# Chasis_2018.net
KiCad netlist of a schematic drawn in EAGLE
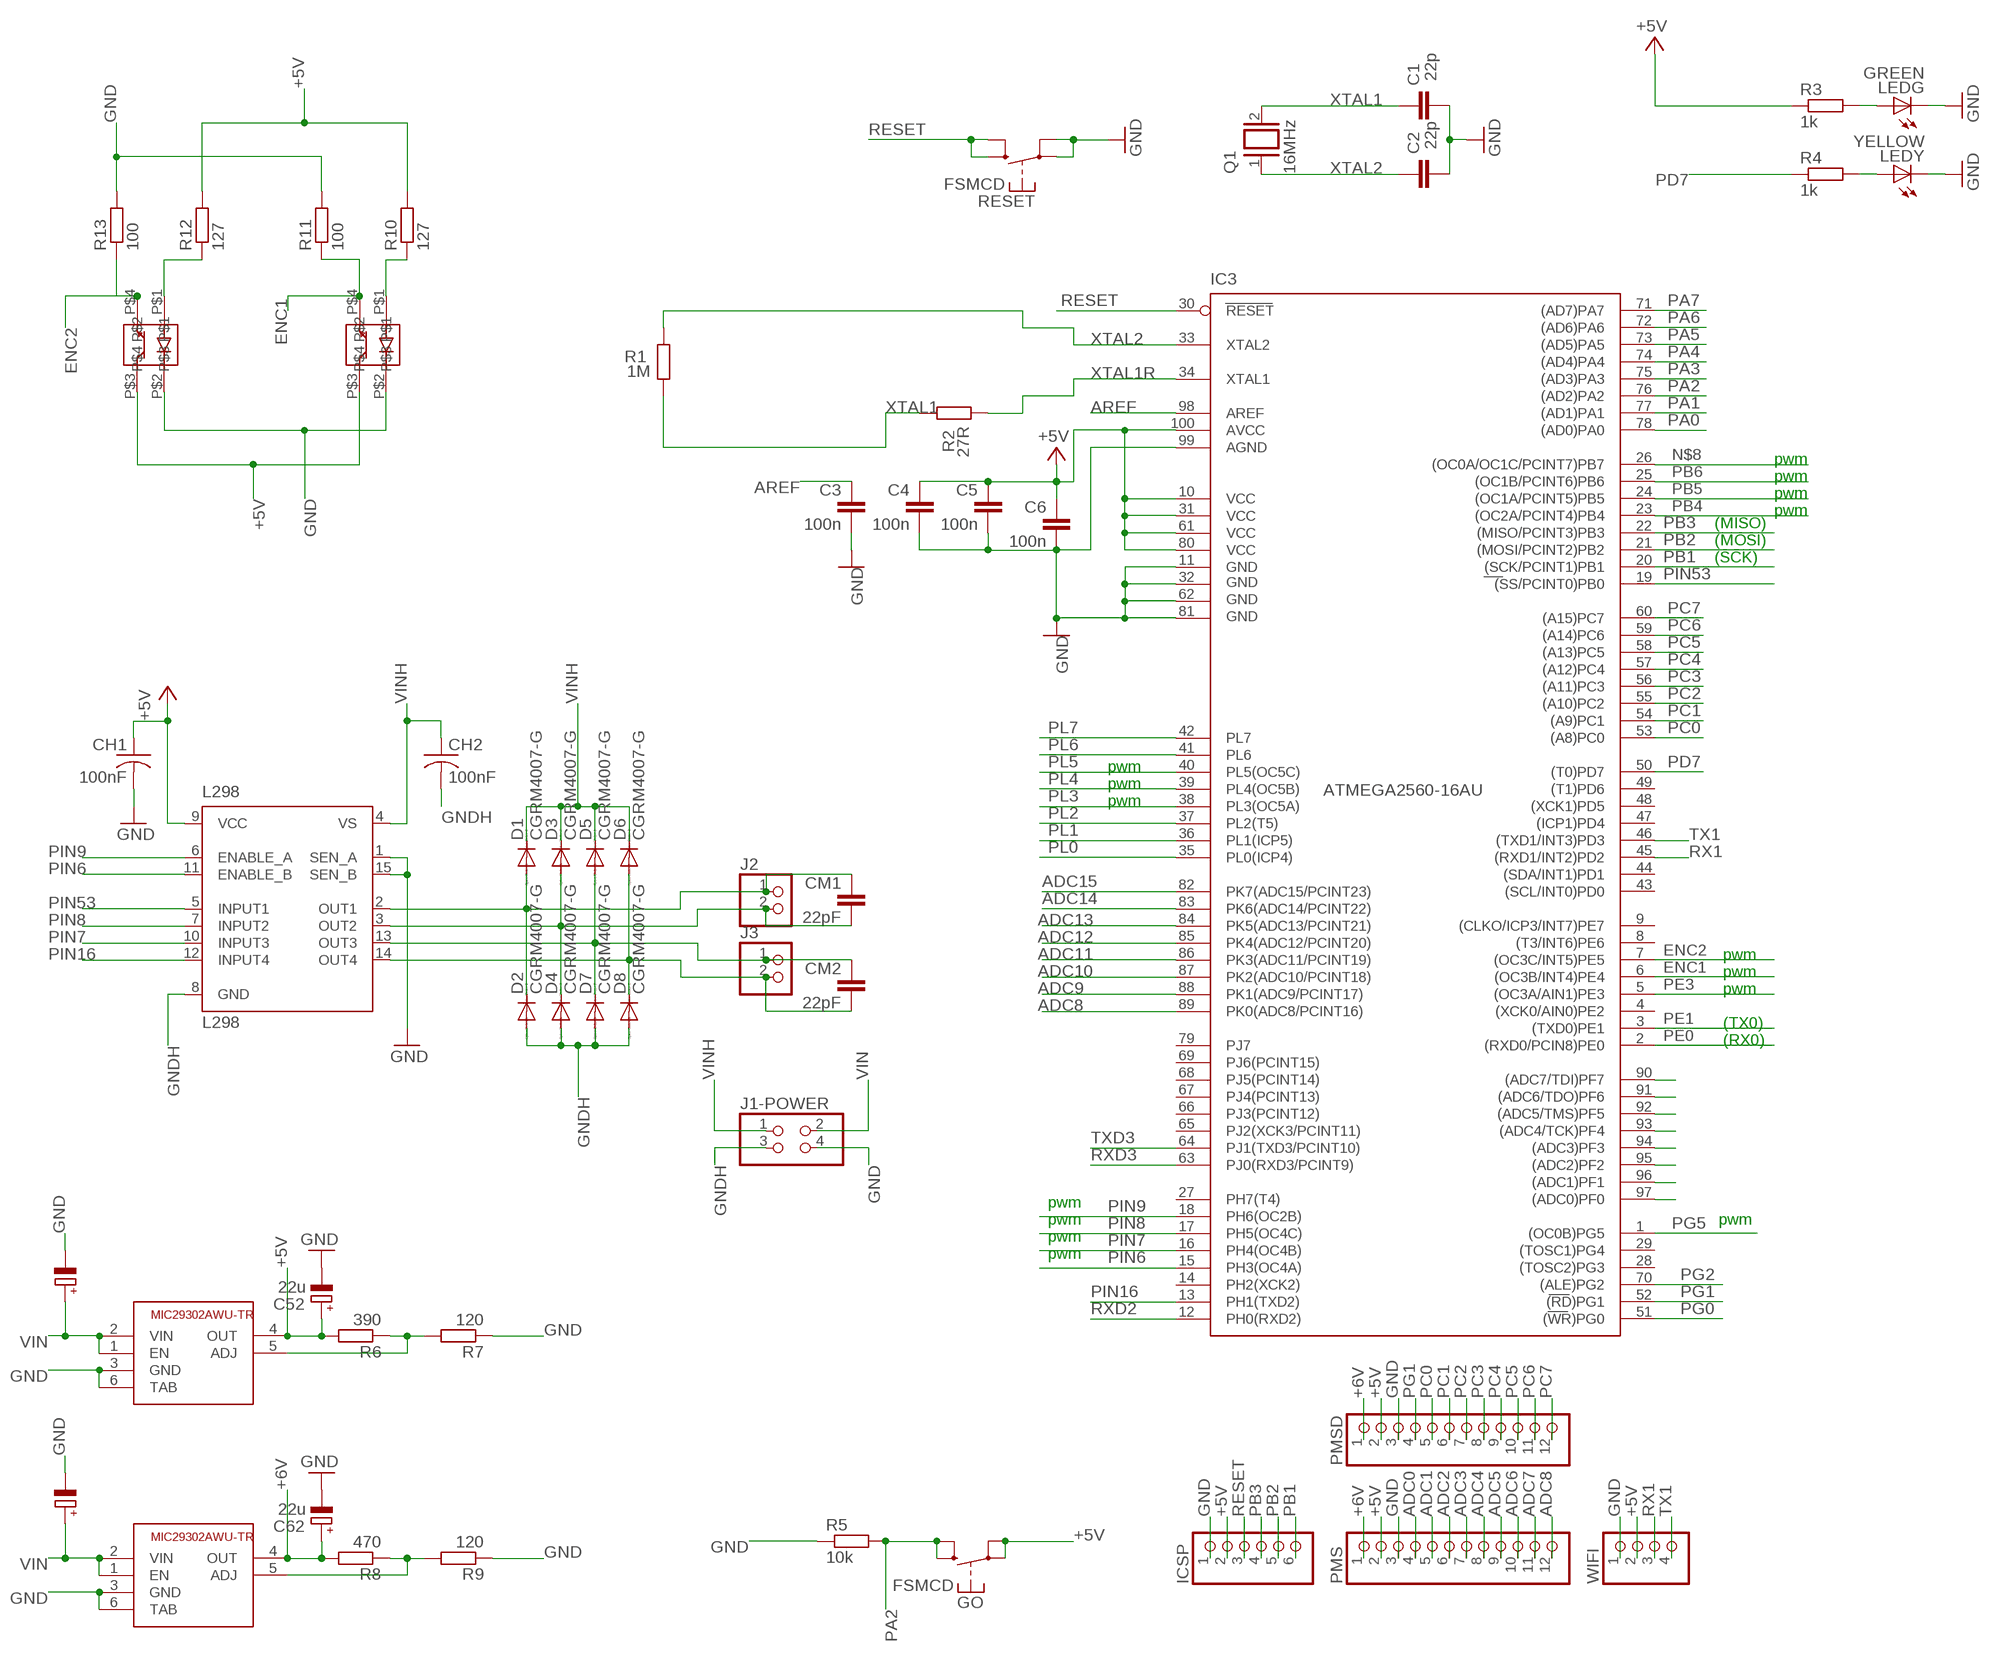
[diagram p0: schematic, sheet 1]

(export (version "E")
  (design (tool "Eeschema 10.0.6"))
  (components
    (comp (ref "C1")
      (value "22p")
      (footprint "eagle-import:C0805K")
      (libsource (lib "eagle-import") (part "C-EUC0805K"))
    )
    (comp (ref "C2")
      (value "22p")
      (footprint "eagle-import:C0805K")
      (libsource (lib "eagle-import") (part "C-EUC0805K"))
    )
    (comp (ref "C3")
      (value "100n")
      (footprint "eagle-import:C0805K")
      (libsource (lib "eagle-import") (part "C-EUC0805K"))
    )
    (comp (ref "C4")
      (value "100n")
      (footprint "eagle-import:C0805K")
      (libsource (lib "eagle-import") (part "C-EUC0805K"))
    )
    (comp (ref "C5")
      (value "100n")
      (footprint "eagle-import:C0805K")
      (libsource (lib "eagle-import") (part "C-EUC0805K"))
    )
    (comp (ref "C6")
      (value "100n")
      (footprint "eagle-import:C0805K")
      (libsource (lib "eagle-import") (part "C-EUC0805K"))
    )
    (comp (ref "C51")
      (value "10u")
      (footprint "eagle-import:PANASONIC_D")
      (libsource (lib "eagle-import") (part "CPOL-EUD"))
    )
    (comp (ref "C52")
      (value "22u")
      (footprint "eagle-import:PANASONIC_D")
      (libsource (lib "eagle-import") (part "CPOL-EUD"))
    )
    (comp (ref "C61")
      (value "10u")
      (footprint "eagle-import:PANASONIC_D")
      (libsource (lib "eagle-import") (part "CPOL-EUD"))
    )
    (comp (ref "C62")
      (value "22u")
      (footprint "eagle-import:PANASONIC_D")
      (libsource (lib "eagle-import") (part "CPOL-EUD"))
    )
    (comp (ref "CH1")
      (value "100nF")
      (footprint "eagle-import:C0805K")
      (libsource (lib "eagle-import") (part "C-USC0805K"))
    )
    (comp (ref "CH2")
      (value "100nF")
      (footprint "eagle-import:C0805K")
      (libsource (lib "eagle-import") (part "C-USC0805K"))
    )
    (comp (ref "CM1")
      (value "22pF")
      (footprint "eagle-import:C1206K")
      (libsource (lib "eagle-import") (part "C-EUC1206K"))
    )
    (comp (ref "CM2")
      (value "22pF")
      (footprint "eagle-import:C1206K")
      (libsource (lib "eagle-import") (part "C-EUC1206K"))
    )
    (comp (ref "D1")
      (value "CGRM4007-G")
      (footprint "eagle-import:SOD-123_MINI-SMA")
      (libsource (lib "eagle-import") (part "CGRM400-G7"))
    )
    (comp (ref "D2")
      (value "CGRM4007-G")
      (footprint "eagle-import:SOD-123_MINI-SMA")
      (libsource (lib "eagle-import") (part "CGRM400-G7"))
    )
    (comp (ref "D3")
      (value "CGRM4007-G")
      (footprint "eagle-import:SOD-123_MINI-SMA")
      (libsource (lib "eagle-import") (part "CGRM400-G7"))
    )
    (comp (ref "D4")
      (value "CGRM4007-G")
      (footprint "eagle-import:SOD-123_MINI-SMA")
      (libsource (lib "eagle-import") (part "CGRM400-G7"))
    )
    (comp (ref "D5")
      (value "CGRM4007-G")
      (footprint "eagle-import:SOD-123_MINI-SMA")
      (libsource (lib "eagle-import") (part "CGRM400-G7"))
    )
    (comp (ref "D6")
      (value "CGRM4007-G")
      (footprint "eagle-import:SOD-123_MINI-SMA")
      (libsource (lib "eagle-import") (part "CGRM400-G7"))
    )
    (comp (ref "D7")
      (value "CGRM4007-G")
      (footprint "eagle-import:SOD-123_MINI-SMA")
      (libsource (lib "eagle-import") (part "CGRM400-G7"))
    )
    (comp (ref "D8")
      (value "CGRM4007-G")
      (footprint "eagle-import:SOD-123_MINI-SMA")
      (libsource (lib "eagle-import") (part "CGRM400-G7"))
    )
    (comp (ref "ENC1")
      (value "EE-SX1046")
      (footprint "eagle-import:EE-SX1046")
      (libsource (lib "eagle-import") (part "EE-SX1046"))
    )
    (comp (ref "ENC2")
      (value "EE-SX1046")
      (footprint "eagle-import:EE-SX1046")
      (libsource (lib "eagle-import") (part "EE-SX1046"))
    )
    (comp (ref "GO")
      (value "FSMCD")
      (footprint "eagle-import:FSMCD")
      (libsource (lib "eagle-import") (part "FSMCD"))
    )
    (comp (ref "IC3")
      (value "ATMEGA2560-16AU")
      (footprint "eagle-import:TQFP100")
      (libsource (lib "eagle-import") (part "ATMEGAAU1280-16"))
    )
    (comp (ref "ICSP")
      (value "PINHD-1X6")
      (footprint "eagle-import:1X06")
      (libsource (lib "eagle-import") (part "PINHD-1X6"))
    )
    (comp (ref "J1-POWER")
      (value "PINHD-2X2")
      (footprint "eagle-import:2X02")
      (libsource (lib "eagle-import") (part "PINHD-2X2"))
    )
    (comp (ref "J2")
      (value "PINHD-1X2")
      (footprint "eagle-import:1X02")
      (libsource (lib "eagle-import") (part "PINHD-1X2"))
    )
    (comp (ref "J3")
      (value "PINHD-1X2")
      (footprint "eagle-import:1X02")
      (libsource (lib "eagle-import") (part "PINHD-1X2"))
    )
    (comp (ref "L298")
      (value "L298")
      (footprint "eagle-import:MULTIWATT-15")
      (fields (field (name "MPN") "L298N"))
      (libsource (lib "eagle-import") (part "L298"))
    )
    (comp (ref "LEDG")
      (value "GREEN")
      (footprint "eagle-import:CHIP-LED0805")
      (libsource (lib "eagle-import") (part "LEDCHIP-LED0805"))
    )
    (comp (ref "LEDY")
      (value "YELLOW")
      (footprint "eagle-import:CHIP-LED0805")
      (libsource (lib "eagle-import") (part "LEDCHIP-LED0805"))
    )
    (comp (ref "PMS")
      (value "PINHD-1X12")
      (footprint "eagle-import:1X12")
      (libsource (lib "eagle-import") (part "PINHD-1X12"))
    )
    (comp (ref "PMSD")
      (value "PINHD-1X12")
      (footprint "eagle-import:1X12")
      (libsource (lib "eagle-import") (part "PINHD-1X12"))
    )
    (comp (ref "Q1")
      (value "16MHz")
      (footprint "eagle-import:QS")
      (libsource (lib "eagle-import") (part "XTAL/S"))
    )
    (comp (ref "R1")
      (value "1M")
      (footprint "eagle-import:R0805W")
      (libsource (lib "eagle-import") (part "R-EU_R0805W"))
    )
    (comp (ref "R2")
      (value "27R")
      (footprint "eagle-import:R0805W")
      (libsource (lib "eagle-import") (part "R-EU_R0805W"))
    )
    (comp (ref "R3")
      (value "1k")
      (footprint "eagle-import:R0805W")
      (libsource (lib "eagle-import") (part "resistor_348_R-EU_R0805W"))
    )
    (comp (ref "R4")
      (value "1k")
      (footprint "eagle-import:R0805W")
      (libsource (lib "eagle-import") (part "resistor_348_R-EU_R0805W"))
    )
    (comp (ref "R5")
      (value "10k")
      (footprint "eagle-import:R0805W")
      (libsource (lib "eagle-import") (part "resistor_348_R-EU_R0805W"))
    )
    (comp (ref "R6")
      (value "390")
      (footprint "eagle-import:R0805W")
      (libsource (lib "eagle-import") (part "resistor_348_R-EU_R0805W"))
    )
    (comp (ref "R7")
      (value "120")
      (footprint "eagle-import:R0805W")
      (libsource (lib "eagle-import") (part "resistor_348_R-EU_R0805W"))
    )
    (comp (ref "R8")
      (value "470")
      (footprint "eagle-import:R0805W")
      (libsource (lib "eagle-import") (part "resistor_348_R-EU_R0805W"))
    )
    (comp (ref "R9")
      (value "120")
      (footprint "eagle-import:R0805W")
      (libsource (lib "eagle-import") (part "resistor_348_R-EU_R0805W"))
    )
    (comp (ref "R10")
      (value "127")
      (footprint "eagle-import:R0805W")
      (libsource (lib "eagle-import") (part "resistor_348_R-EU_R0805W"))
    )
    (comp (ref "R11")
      (value "100")
      (footprint "eagle-import:R0805W")
      (libsource (lib "eagle-import") (part "resistor_348_R-EU_R0805W"))
    )
    (comp (ref "R12")
      (value "127")
      (footprint "eagle-import:R0805W")
      (libsource (lib "eagle-import") (part "resistor_348_R-EU_R0805W"))
    )
    (comp (ref "R13")
      (value "100")
      (footprint "eagle-import:R0805W")
      (libsource (lib "eagle-import") (part "resistor_348_R-EU_R0805W"))
    )
    (comp (ref "REG5V")
      (value "MIC29302AWU-TR")
      (footprint "eagle-import:TO263-5")
      (fields (field (name "MF") "Microchip"))
      (libsource (lib "eagle-import") (part "MIC29302AWU-TR"))
    )
    (comp (ref "REG6V")
      (value "MIC29302AWU-TR")
      (footprint "eagle-import:TO263-5")
      (fields (field (name "MF") "Microchip") (field (name "SPICEPREFIX") "X"))
      (libsource (lib "eagle-import") (part "MIC29302AWU-TR"))
    )
    (comp (ref "RESET")
      (value "FSMCD")
      (footprint "eagle-import:FSMCD")
      (libsource (lib "eagle-import") (part "FSMCD"))
    )
    (comp (ref "WIFI")
      (value "PINHD-1X4")
      (footprint "eagle-import:1X04")
      (libsource (lib "eagle-import") (part "PINHD-1X4"))
    )
  )
  (nets
    (net (code "1") (name "+5V") (class "Default")
      (node (ref "C4") (pin "1") (pinfunction "1_1") (pintype "passive"))
      (node (ref "C5") (pin "1") (pinfunction "1_1") (pintype "passive"))
      (node (ref "C52") (pin "+") (pinfunction "+_+") (pintype "passive"))
      (node (ref "C6") (pin "1") (pinfunction "1_1") (pintype "passive"))
      (node (ref "CH1") (pin "1") (pinfunction "1_1") (pintype "passive"))
      (node (ref "ENC1") (pin "P$3") (pinfunction "P$2_P$3") (pintype "bidirectional"))
      (node (ref "ENC2") (pin "P$3") (pinfunction "P$2_P$3") (pintype "bidirectional"))
      (node (ref "GO") (pin "P$1") (pinfunction "P_P$1") (pintype "passive"))
      (node (ref "GO") (pin "P$2") (pinfunction "P_P$2") (pintype "passive"))
      (node (ref "IC3") (pin "10") (pinfunction "VCC_10") (pintype "power_in"))
      (node (ref "IC3") (pin "100") (pinfunction "AVCC_100") (pintype "power_in"))
      (node (ref "IC3") (pin "31") (pinfunction "VCC1_31") (pintype "power_in"))
      (node (ref "IC3") (pin "61") (pinfunction "VCC2_61") (pintype "power_in"))
      (node (ref "IC3") (pin "80") (pinfunction "VCC3_80") (pintype "power_in"))
      (node (ref "ICSP") (pin "2") (pinfunction "2_2") (pintype "passive"))
      (node (ref "L298") (pin "9") (pinfunction "VCC_9") (pintype "power_in"))
      (node (ref "PMS") (pin "2") (pinfunction "2_2") (pintype "passive"))
      (node (ref "PMSD") (pin "2") (pinfunction "2_2") (pintype "passive"))
      (node (ref "R10") (pin "2") (pinfunction "2_2") (pintype "passive"))
      (node (ref "R12") (pin "2") (pinfunction "2_2") (pintype "passive"))
      (node (ref "R3") (pin "1") (pinfunction "1_1") (pintype "passive"))
      (node (ref "R6") (pin "2") (pinfunction "2_2") (pintype "passive"))
      (node (ref "REG5V") (pin "4") (pinfunction "OUT_4") (pintype "bidirectional"))
      (node (ref "WIFI") (pin "2") (pinfunction "2_2") (pintype "passive"))
    )
    (net (code "2") (name "/+6V") (class "Default")
      (node (ref "C62") (pin "+") (pinfunction "+_+") (pintype "passive"))
      (node (ref "PMS") (pin "1") (pinfunction "1_1") (pintype "passive"))
      (node (ref "PMSD") (pin "1") (pinfunction "1_1") (pintype "passive"))
      (node (ref "R8") (pin "2") (pinfunction "2_2") (pintype "passive"))
      (node (ref "REG6V") (pin "4") (pinfunction "OUT_4") (pintype "bidirectional"))
    )
    (net (code "3") (name "/ADC0") (class "Default")
      (node (ref "IC3") (pin "97") (pinfunction "(ADC0)PF0_97") (pintype "bidirectional"))
      (node (ref "PMS") (pin "4") (pinfunction "4_4") (pintype "passive"))
    )
    (net (code "4") (name "/ADC1") (class "Default")
      (node (ref "IC3") (pin "96") (pinfunction "(ADC1)PF1_96") (pintype "bidirectional"))
      (node (ref "PMS") (pin "5") (pinfunction "5_5") (pintype "passive"))
    )
    (net (code "5") (name "/ADC2") (class "Default")
      (node (ref "IC3") (pin "95") (pinfunction "(ADC2)PF2_95") (pintype "bidirectional"))
      (node (ref "PMS") (pin "6") (pinfunction "6_6") (pintype "passive"))
    )
    (net (code "6") (name "/ADC3") (class "Default")
      (node (ref "IC3") (pin "94") (pinfunction "(ADC3)PF3_94") (pintype "bidirectional"))
      (node (ref "PMS") (pin "7") (pinfunction "7_7") (pintype "passive"))
    )
    (net (code "7") (name "/ADC4") (class "Default")
      (node (ref "IC3") (pin "93") (pinfunction "(ADC4/TCK)PF4_93") (pintype "bidirectional"))
      (node (ref "PMS") (pin "8") (pinfunction "8_8") (pintype "passive"))
    )
    (net (code "8") (name "/ADC5") (class "Default")
      (node (ref "IC3") (pin "92") (pinfunction "(ADC5/TMS)PF5_92") (pintype "bidirectional"))
      (node (ref "PMS") (pin "9") (pinfunction "9_9") (pintype "passive"))
    )
    (net (code "9") (name "/ADC6") (class "Default")
      (node (ref "IC3") (pin "91") (pinfunction "(ADC6/TDO)PF6_91") (pintype "bidirectional"))
      (node (ref "PMS") (pin "10") (pinfunction "10_10") (pintype "passive"))
    )
    (net (code "10") (name "/ADC7") (class "Default")
      (node (ref "IC3") (pin "90") (pinfunction "(ADC7/TDI)PF7_90") (pintype "bidirectional"))
      (node (ref "PMS") (pin "11") (pinfunction "11_11") (pintype "passive"))
    )
    (net (code "11") (name "/ADC8") (class "Default")
      (node (ref "IC3") (pin "89") (pinfunction "PK0(ADC8/PCINT16)_89") (pintype "bidirectional"))
      (node (ref "PMS") (pin "12") (pinfunction "12_12") (pintype "passive"))
    )
    (net (code "12") (name "/ADC9") (class "Default")
      (node (ref "IC3") (pin "88") (pinfunction "PK1(ADC9/PCINT17)_88") (pintype "bidirectional"))
    )
    (net (code "13") (name "/ADC10") (class "Default")
      (node (ref "IC3") (pin "87") (pinfunction "PK2(ADC10/PCINT18)_87") (pintype "bidirectional"))
    )
    (net (code "14") (name "/ADC11") (class "Default")
      (node (ref "IC3") (pin "86") (pinfunction "PK3(ADC11/PCINT19)_86") (pintype "bidirectional"))
    )
    (net (code "15") (name "/ADC12") (class "Default")
      (node (ref "IC3") (pin "85") (pinfunction "PK4(ADC12/PCINT20)_85") (pintype "bidirectional"))
    )
    (net (code "16") (name "/ADC13") (class "Default")
      (node (ref "IC3") (pin "84") (pinfunction "PK5(ADC13/PCINT21)_84") (pintype "bidirectional"))
    )
    (net (code "17") (name "/ADC14") (class "Default")
      (node (ref "IC3") (pin "83") (pinfunction "PK6(ADC14/PCINT22)_83") (pintype "bidirectional"))
    )
    (net (code "18") (name "/ADC15") (class "Default")
      (node (ref "IC3") (pin "82") (pinfunction "PK7(ADC15/PCINT23)_82") (pintype "bidirectional"))
    )
    (net (code "19") (name "/AREF") (class "Default")
      (node (ref "C3") (pin "1") (pinfunction "1_1") (pintype "passive"))
      (node (ref "IC3") (pin "98") (pinfunction "AREF_98") (pintype "bidirectional"))
    )
    (net (code "20") (name "/ENC1") (class "Default")
      (node (ref "ENC2") (pin "P$4") (pinfunction "P$4_P$4") (pintype "bidirectional"))
      (node (ref "IC3") (pin "6") (pinfunction "(OC3B/INT4)PE4_6") (pintype "bidirectional"))
      (node (ref "R11") (pin "1") (pinfunction "1_1") (pintype "passive"))
    )
    (net (code "21") (name "/ENC2") (class "Default")
      (node (ref "ENC1") (pin "P$4") (pinfunction "P$4_P$4") (pintype "bidirectional"))
      (node (ref "IC3") (pin "7") (pinfunction "(OC3C/INT5)PE5_7") (pintype "bidirectional"))
      (node (ref "R13") (pin "1") (pinfunction "1_1") (pintype "passive"))
    )
    (net (code "22") (name "/GNDH") (class "Default")
      (node (ref "CH2") (pin "2") (pinfunction "2_2") (pintype "passive"))
      (node (ref "D2") (pin "A") (pinfunction "A_A") (pintype "passive"))
      (node (ref "D4") (pin "A") (pinfunction "A_A") (pintype "passive"))
      (node (ref "D7") (pin "A") (pinfunction "A_A") (pintype "passive"))
      (node (ref "D8") (pin "A") (pinfunction "A_A") (pintype "passive"))
      (node (ref "J1-POWER") (pin "3") (pinfunction "3_3") (pintype "passive"))
      (node (ref "L298") (pin "8") (pinfunction "GND_8") (pintype "power_in"))
    )
    (net (code "23") (name "/N$8") (class "Default")
      (node (ref "IC3") (pin "26") (pinfunction "(OC0A/OC1C/PCINT7)PB7_26") (pintype "bidirectional"))
    )
    (net (code "24") (name "/PA0") (class "Default")
      (node (ref "IC3") (pin "78") (pinfunction "(AD0)PA0_78") (pintype "bidirectional"))
    )
    (net (code "25") (name "/PA1") (class "Default")
      (node (ref "IC3") (pin "77") (pinfunction "(AD1)PA1_77") (pintype "bidirectional"))
    )
    (net (code "26") (name "/PA2") (class "Default")
      (node (ref "GO") (pin "P$3") (pinfunction "S_P$3") (pintype "passive"))
      (node (ref "GO") (pin "P$4") (pinfunction "S_P$4") (pintype "passive"))
      (node (ref "IC3") (pin "76") (pinfunction "(AD2)PA2_76") (pintype "bidirectional"))
      (node (ref "R5") (pin "2") (pinfunction "2_2") (pintype "passive"))
    )
    (net (code "27") (name "/PA3") (class "Default")
      (node (ref "IC3") (pin "75") (pinfunction "(AD3)PA3_75") (pintype "bidirectional"))
    )
    (net (code "28") (name "/PA4") (class "Default")
      (node (ref "IC3") (pin "74") (pinfunction "(AD4)PA4_74") (pintype "bidirectional"))
    )
    (net (code "29") (name "/PA5") (class "Default")
      (node (ref "IC3") (pin "73") (pinfunction "(AD5)PA5_73") (pintype "bidirectional"))
    )
    (net (code "30") (name "/PA6") (class "Default")
      (node (ref "IC3") (pin "72") (pinfunction "(AD6)PA6_72") (pintype "bidirectional"))
    )
    (net (code "31") (name "/PA7") (class "Default")
      (node (ref "IC3") (pin "71") (pinfunction "(AD7)PA7_71") (pintype "bidirectional"))
    )
    (net (code "32") (name "/PB1") (class "Default")
      (node (ref "IC3") (pin "20") (pinfunction "(SCK/PCINT1)PB1_20") (pintype "bidirectional"))
      (node (ref "ICSP") (pin "6") (pinfunction "6_6") (pintype "passive"))
    )
    (net (code "33") (name "/PB2") (class "Default")
      (node (ref "IC3") (pin "21") (pinfunction "(MOSI/PCINT2)PB2_21") (pintype "bidirectional"))
      (node (ref "ICSP") (pin "5") (pinfunction "5_5") (pintype "passive"))
    )
    (net (code "34") (name "/PB3") (class "Default")
      (node (ref "IC3") (pin "22") (pinfunction "(MISO/PCINT3)PB3_22") (pintype "bidirectional"))
      (node (ref "ICSP") (pin "4") (pinfunction "4_4") (pintype "passive"))
    )
    (net (code "35") (name "/PB4") (class "Default")
      (node (ref "IC3") (pin "23") (pinfunction "(OC2A/PCINT4)PB4_23") (pintype "bidirectional"))
    )
    (net (code "36") (name "/PB5") (class "Default")
      (node (ref "IC3") (pin "24") (pinfunction "(OC1A/PCINT5)PB5_24") (pintype "bidirectional"))
    )
    (net (code "37") (name "/PB6") (class "Default")
      (node (ref "IC3") (pin "25") (pinfunction "(OC1B/PCINT6)PB6_25") (pintype "bidirectional"))
    )
    (net (code "38") (name "/PC0") (class "Default")
      (node (ref "IC3") (pin "53") (pinfunction "(A8)PC0_53") (pintype "bidirectional"))
      (node (ref "PMSD") (pin "5") (pinfunction "5_5") (pintype "passive"))
    )
    (net (code "39") (name "/PC1") (class "Default")
      (node (ref "IC3") (pin "54") (pinfunction "(A9)PC1_54") (pintype "bidirectional"))
      (node (ref "PMSD") (pin "6") (pinfunction "6_6") (pintype "passive"))
    )
    (net (code "40") (name "/PC2") (class "Default")
      (node (ref "IC3") (pin "55") (pinfunction "(A10)PC2_55") (pintype "bidirectional"))
      (node (ref "PMSD") (pin "7") (pinfunction "7_7") (pintype "passive"))
    )
    (net (code "41") (name "/PC3") (class "Default")
      (node (ref "IC3") (pin "56") (pinfunction "(A11)PC3_56") (pintype "bidirectional"))
      (node (ref "PMSD") (pin "8") (pinfunction "8_8") (pintype "passive"))
    )
    (net (code "42") (name "/PC4") (class "Default")
      (node (ref "IC3") (pin "57") (pinfunction "(A12)PC4_57") (pintype "bidirectional"))
      (node (ref "PMSD") (pin "9") (pinfunction "9_9") (pintype "passive"))
    )
    (net (code "43") (name "/PC5") (class "Default")
      (node (ref "IC3") (pin "58") (pinfunction "(A13)PC5_58") (pintype "bidirectional"))
      (node (ref "PMSD") (pin "10") (pinfunction "10_10") (pintype "passive"))
    )
    (net (code "44") (name "/PC6") (class "Default")
      (node (ref "IC3") (pin "59") (pinfunction "(A14)PC6_59") (pintype "bidirectional"))
      (node (ref "PMSD") (pin "11") (pinfunction "11_11") (pintype "passive"))
    )
    (net (code "45") (name "/PC7") (class "Default")
      (node (ref "IC3") (pin "60") (pinfunction "(A15)PC7_60") (pintype "bidirectional"))
      (node (ref "PMSD") (pin "12") (pinfunction "12_12") (pintype "passive"))
    )
    (net (code "46") (name "/PD7") (class "Default")
      (node (ref "IC3") (pin "50") (pinfunction "(T0)PD7_50") (pintype "bidirectional"))
      (node (ref "R4") (pin "1") (pinfunction "1_1") (pintype "passive"))
    )
    (net (code "47") (name "/PE0") (class "Default")
      (node (ref "IC3") (pin "2") (pinfunction "(RXD0/PCIN8)PE0_2") (pintype "bidirectional"))
    )
    (net (code "48") (name "/PE1") (class "Default")
      (node (ref "IC3") (pin "3") (pinfunction "(TXD0)PE1_3") (pintype "bidirectional"))
    )
    (net (code "49") (name "/PE3") (class "Default")
      (node (ref "IC3") (pin "5") (pinfunction "(OC3A/AIN1)PE3_5") (pintype "bidirectional"))
    )
    (net (code "50") (name "/PG0") (class "Default")
      (node (ref "IC3") (pin "51") (pinfunction "(WR)PG0_51") (pintype "bidirectional"))
    )
    (net (code "51") (name "/PG1") (class "Default")
      (node (ref "IC3") (pin "52") (pinfunction "(RD)PG1_52") (pintype "bidirectional"))
      (node (ref "PMSD") (pin "4") (pinfunction "4_4") (pintype "passive"))
    )
    (net (code "52") (name "/PG2") (class "Default")
      (node (ref "IC3") (pin "70") (pinfunction "(ALE)PG2_70") (pintype "bidirectional"))
    )
    (net (code "53") (name "/PG5") (class "Default")
      (node (ref "IC3") (pin "1") (pinfunction "(OC0B)PG5_1") (pintype "bidirectional"))
    )
    (net (code "54") (name "/PIN6") (class "Default")
      (node (ref "IC3") (pin "15") (pinfunction "PH3(OC4A)_15") (pintype "bidirectional"))
      (node (ref "L298") (pin "11") (pinfunction "ENABLE_B_11") (pintype "input"))
    )
    (net (code "55") (name "/PIN7") (class "Default")
      (node (ref "IC3") (pin "16") (pinfunction "PH4(OC4B)_16") (pintype "bidirectional"))
      (node (ref "L298") (pin "10") (pinfunction "INPUT3_10") (pintype "input"))
    )
    (net (code "56") (name "/PIN8") (class "Default")
      (node (ref "IC3") (pin "17") (pinfunction "PH5(OC4C)_17") (pintype "bidirectional"))
      (node (ref "L298") (pin "7") (pinfunction "INPUT2_7") (pintype "input"))
    )
    (net (code "57") (name "/PIN9") (class "Default")
      (node (ref "IC3") (pin "18") (pinfunction "PH6(OC2B)_18") (pintype "bidirectional"))
      (node (ref "L298") (pin "6") (pinfunction "ENABLE_A_6") (pintype "input"))
    )
    (net (code "58") (name "/PIN16") (class "Default")
      (node (ref "IC3") (pin "13") (pinfunction "PH1(TXD2)_13") (pintype "bidirectional"))
      (node (ref "L298") (pin "12") (pinfunction "INPUT4_12") (pintype "input"))
    )
    (net (code "59") (name "/PIN53") (class "Default")
      (node (ref "IC3") (pin "19") (pinfunction "(SS/PCINT0)PB0_19") (pintype "bidirectional"))
      (node (ref "L298") (pin "5") (pinfunction "INPUT1_5") (pintype "input"))
    )
    (net (code "60") (name "/PL0") (class "Default")
      (node (ref "IC3") (pin "35") (pinfunction "PL0(ICP4)_35") (pintype "bidirectional"))
    )
    (net (code "61") (name "/PL1") (class "Default")
      (node (ref "IC3") (pin "36") (pinfunction "PL1(ICP5)_36") (pintype "bidirectional"))
    )
    (net (code "62") (name "/PL2") (class "Default")
      (node (ref "IC3") (pin "37") (pinfunction "PL2(T5)_37") (pintype "bidirectional"))
    )
    (net (code "63") (name "/PL3") (class "Default")
      (node (ref "IC3") (pin "38") (pinfunction "PL3(OC5A)_38") (pintype "bidirectional"))
    )
    (net (code "64") (name "/PL4") (class "Default")
      (node (ref "IC3") (pin "39") (pinfunction "PL4(OC5B)_39") (pintype "bidirectional"))
    )
    (net (code "65") (name "/PL5") (class "Default")
      (node (ref "IC3") (pin "40") (pinfunction "PL5(OC5C)_40") (pintype "bidirectional"))
    )
    (net (code "66") (name "/PL6") (class "Default")
      (node (ref "IC3") (pin "41") (pinfunction "PL6_41") (pintype "bidirectional"))
    )
    (net (code "67") (name "/PL7") (class "Default")
      (node (ref "IC3") (pin "42") (pinfunction "PL7_42") (pintype "bidirectional"))
    )
    (net (code "68") (name "/RESET") (class "Default")
      (node (ref "IC3") (pin "30") (pinfunction "RESET_30") (pintype "input"))
      (node (ref "ICSP") (pin "3") (pinfunction "3_3") (pintype "passive"))
      (node (ref "RESET") (pin "P$3") (pinfunction "S_P$3") (pintype "passive"))
      (node (ref "RESET") (pin "P$4") (pinfunction "S_P$4") (pintype "passive"))
    )
    (net (code "69") (name "/RX1") (class "Default")
      (node (ref "IC3") (pin "45") (pinfunction "(RXD1/INT2)PD2_45") (pintype "bidirectional"))
      (node (ref "WIFI") (pin "3") (pinfunction "3_3") (pintype "passive"))
    )
    (net (code "70") (name "/RXD2") (class "Default")
      (node (ref "IC3") (pin "12") (pinfunction "PH0(RXD2)_12") (pintype "bidirectional"))
    )
    (net (code "71") (name "/RXD3") (class "Default")
      (node (ref "IC3") (pin "63") (pinfunction "PJ0(RXD3/PCINT9)_63") (pintype "bidirectional"))
    )
    (net (code "72") (name "/TX1") (class "Default")
      (node (ref "IC3") (pin "46") (pinfunction "(TXD1/INT3)PD3_46") (pintype "bidirectional"))
      (node (ref "WIFI") (pin "4") (pinfunction "4_4") (pintype "passive"))
    )
    (net (code "73") (name "/TXD3") (class "Default")
      (node (ref "IC3") (pin "64") (pinfunction "PJ1(TXD3/PCINT10)_64") (pintype "bidirectional"))
    )
    (net (code "74") (name "/VIN") (class "Default")
      (node (ref "C51") (pin "+") (pinfunction "+_+") (pintype "passive"))
      (node (ref "C61") (pin "+") (pinfunction "+_+") (pintype "passive"))
      (node (ref "J1-POWER") (pin "2") (pinfunction "2_2") (pintype "passive"))
      (node (ref "REG5V") (pin "1") (pinfunction "EN_1") (pintype "bidirectional"))
      (node (ref "REG5V") (pin "2") (pinfunction "VIN_2") (pintype "bidirectional"))
      (node (ref "REG6V") (pin "1") (pinfunction "EN_1") (pintype "bidirectional"))
      (node (ref "REG6V") (pin "2") (pinfunction "VIN_2") (pintype "bidirectional"))
    )
    (net (code "75") (name "/VINH") (class "Default")
      (node (ref "CH2") (pin "1") (pinfunction "1_1") (pintype "passive"))
      (node (ref "D1") (pin "C") (pinfunction "C_C") (pintype "passive"))
      (node (ref "D3") (pin "C") (pinfunction "C_C") (pintype "passive"))
      (node (ref "D5") (pin "C") (pinfunction "C_C") (pintype "passive"))
      (node (ref "D6") (pin "C") (pinfunction "C_C") (pintype "passive"))
      (node (ref "J1-POWER") (pin "1") (pinfunction "1_1") (pintype "passive"))
      (node (ref "L298") (pin "4") (pinfunction "VS_4") (pintype "power_in"))
    )
    (net (code "76") (name "/XTAL1") (class "Default")
      (node (ref "C1") (pin "2") (pinfunction "2_2") (pintype "passive"))
      (node (ref "Q1") (pin "2") (pinfunction "2_2") (pintype "passive"))
      (node (ref "R1") (pin "1") (pinfunction "1_1") (pintype "passive"))
      (node (ref "R2") (pin "2") (pinfunction "2_2") (pintype "passive"))
    )
    (net (code "77") (name "/XTAL1R") (class "Default")
      (node (ref "IC3") (pin "34") (pinfunction "XTAL1_34") (pintype "input"))
      (node (ref "R2") (pin "1") (pinfunction "1_1") (pintype "passive"))
    )
    (net (code "78") (name "/XTAL2") (class "Default")
      (node (ref "C2") (pin "2") (pinfunction "2_2") (pintype "passive"))
      (node (ref "IC3") (pin "33") (pinfunction "XTAL2_33") (pintype "output"))
      (node (ref "Q1") (pin "1") (pinfunction "1_1") (pintype "passive"))
      (node (ref "R1") (pin "2") (pinfunction "2_2") (pintype "passive"))
    )
    (net (code "79") (name "GND") (class "Default")
      (node (ref "C1") (pin "1") (pinfunction "1_1") (pintype "passive"))
      (node (ref "C2") (pin "1") (pinfunction "1_1") (pintype "passive"))
      (node (ref "C3") (pin "2") (pinfunction "2_2") (pintype "passive"))
      (node (ref "C4") (pin "2") (pinfunction "2_2") (pintype "passive"))
      (node (ref "C5") (pin "2") (pinfunction "2_2") (pintype "passive"))
      (node (ref "C51") (pin "-") (pinfunction "-_-") (pintype "passive"))
      (node (ref "C52") (pin "-") (pinfunction "-_-") (pintype "passive"))
      (node (ref "C6") (pin "2") (pinfunction "2_2") (pintype "passive"))
      (node (ref "C61") (pin "-") (pinfunction "-_-") (pintype "passive"))
      (node (ref "C62") (pin "-") (pinfunction "-_-") (pintype "passive"))
      (node (ref "CH1") (pin "2") (pinfunction "2_2") (pintype "passive"))
      (node (ref "ENC1") (pin "P$2") (pinfunction "P$1_P$2") (pintype "bidirectional"))
      (node (ref "ENC2") (pin "P$2") (pinfunction "P$1_P$2") (pintype "bidirectional"))
      (node (ref "IC3") (pin "11") (pinfunction "GND_11") (pintype "power_in"))
      (node (ref "IC3") (pin "32") (pinfunction "GND1_32") (pintype "power_in"))
      (node (ref "IC3") (pin "62") (pinfunction "GND2_62") (pintype "power_in"))
      (node (ref "IC3") (pin "81") (pinfunction "GND3_81") (pintype "power_in"))
      (node (ref "IC3") (pin "99") (pinfunction "AGND_99") (pintype "power_in"))
      (node (ref "ICSP") (pin "1") (pinfunction "1_1") (pintype "passive"))
      (node (ref "J1-POWER") (pin "4") (pinfunction "4_4") (pintype "passive"))
      (node (ref "L298") (pin "1") (pinfunction "SEN_A_1") (pintype "input"))
      (node (ref "L298") (pin "15") (pinfunction "SEN_B_15") (pintype "input"))
      (node (ref "LEDG") (pin "C") (pinfunction "C_C") (pintype "passive"))
      (node (ref "LEDY") (pin "C") (pinfunction "C_C") (pintype "passive"))
      (node (ref "PMS") (pin "3") (pinfunction "3_3") (pintype "passive"))
      (node (ref "PMSD") (pin "3") (pinfunction "3_3") (pintype "passive"))
      (node (ref "R11") (pin "2") (pinfunction "2_2") (pintype "passive"))
      (node (ref "R13") (pin "2") (pinfunction "2_2") (pintype "passive"))
      (node (ref "R5") (pin "1") (pinfunction "1_1") (pintype "passive"))
      (node (ref "R7") (pin "1") (pinfunction "1_1") (pintype "passive"))
      (node (ref "R9") (pin "1") (pinfunction "1_1") (pintype "passive"))
      (node (ref "REG5V") (pin "3") (pinfunction "GND_3") (pintype "bidirectional"))
      (node (ref "REG5V") (pin "6") (pinfunction "TAB_6") (pintype "bidirectional"))
      (node (ref "REG6V") (pin "3") (pinfunction "GND_3") (pintype "bidirectional"))
      (node (ref "REG6V") (pin "6") (pinfunction "TAB_6") (pintype "bidirectional"))
      (node (ref "RESET") (pin "P$1") (pinfunction "P_P$1") (pintype "passive"))
      (node (ref "RESET") (pin "P$2") (pinfunction "P_P$2") (pintype "passive"))
      (node (ref "WIFI") (pin "1") (pinfunction "1_1") (pintype "passive"))
    )
    (net (code "80") (name "Net-(ENC1-P$3)") (class "Default")
      (node (ref "ENC1") (pin "P$1") (pinfunction "P$3_P$1") (pintype "bidirectional"))
      (node (ref "R12") (pin "1") (pinfunction "1_1") (pintype "passive"))
    )
    (net (code "81") (name "Net-(ENC2-P$3)") (class "Default")
      (node (ref "ENC2") (pin "P$1") (pinfunction "P$3_P$1") (pintype "bidirectional"))
      (node (ref "R10") (pin "1") (pinfunction "1_1") (pintype "passive"))
    )
    (net (code "82") (name "Net-(L298-OUT1)") (class "Default")
      (node (ref "CM1") (pin "1") (pinfunction "1_1") (pintype "passive"))
      (node (ref "D1") (pin "A") (pinfunction "A_A") (pintype "passive"))
      (node (ref "D2") (pin "C") (pinfunction "C_C") (pintype "passive"))
      (node (ref "J2") (pin "1") (pinfunction "1_1") (pintype "passive"))
      (node (ref "L298") (pin "2") (pinfunction "OUT1_2") (pintype "output"))
    )
    (net (code "83") (name "Net-(L298-OUT2)") (class "Default")
      (node (ref "CM1") (pin "2") (pinfunction "2_2") (pintype "passive"))
      (node (ref "D3") (pin "A") (pinfunction "A_A") (pintype "passive"))
      (node (ref "D4") (pin "C") (pinfunction "C_C") (pintype "passive"))
      (node (ref "J2") (pin "2") (pinfunction "2_2") (pintype "passive"))
      (node (ref "L298") (pin "3") (pinfunction "OUT2_3") (pintype "output"))
    )
    (net (code "84") (name "Net-(L298-OUT3)") (class "Default")
      (node (ref "CM2") (pin "1") (pinfunction "1_1") (pintype "passive"))
      (node (ref "D5") (pin "A") (pinfunction "A_A") (pintype "passive"))
      (node (ref "D7") (pin "C") (pinfunction "C_C") (pintype "passive"))
      (node (ref "J3") (pin "1") (pinfunction "1_1") (pintype "passive"))
      (node (ref "L298") (pin "13") (pinfunction "OUT3_13") (pintype "output"))
    )
    (net (code "85") (name "Net-(L298-OUT4)") (class "Default")
      (node (ref "CM2") (pin "2") (pinfunction "2_2") (pintype "passive"))
      (node (ref "D6") (pin "A") (pinfunction "A_A") (pintype "passive"))
      (node (ref "D8") (pin "C") (pinfunction "C_C") (pintype "passive"))
      (node (ref "J3") (pin "2") (pinfunction "2_2") (pintype "passive"))
      (node (ref "L298") (pin "14") (pinfunction "OUT4_14") (pintype "output"))
    )
    (net (code "86") (name "Net-(LEDG-PadA)") (class "Default")
      (node (ref "LEDG") (pin "A") (pinfunction "A_A") (pintype "passive"))
      (node (ref "R3") (pin "2") (pinfunction "2_2") (pintype "passive"))
    )
    (net (code "87") (name "Net-(LEDY-PadA)") (class "Default")
      (node (ref "LEDY") (pin "A") (pinfunction "A_A") (pintype "passive"))
      (node (ref "R4") (pin "2") (pinfunction "2_2") (pintype "passive"))
    )
    (net (code "88") (name "Net-(REG5V-ADJ)") (class "Default")
      (node (ref "R6") (pin "1") (pinfunction "1_1") (pintype "passive"))
      (node (ref "R7") (pin "2") (pinfunction "2_2") (pintype "passive"))
      (node (ref "REG5V") (pin "5") (pinfunction "ADJ_5") (pintype "bidirectional"))
    )
    (net (code "89") (name "Net-(REG6V-ADJ)") (class "Default")
      (node (ref "R8") (pin "1") (pinfunction "1_1") (pintype "passive"))
      (node (ref "R9") (pin "2") (pinfunction "2_2") (pintype "passive"))
      (node (ref "REG6V") (pin "5") (pinfunction "ADJ_5") (pintype "bidirectional"))
    )
    (net (code "90") (name "unconnected-(IC3-(CLKO{slash}ICP3{slash}INT7)PE7-Pad9)") (class "Default")
      (node (ref "IC3") (pin "9") (pinfunction "(CLKO/ICP3/INT7)PE7_9") (pintype "bidirectional"))
    )
    (net (code "91") (name "unconnected-(IC3-(ICP1)PD4-Pad47)") (class "Default")
      (node (ref "IC3") (pin "47") (pinfunction "(ICP1)PD4_47") (pintype "bidirectional"))
    )
    (net (code "92") (name "unconnected-(IC3-(SCL{slash}INT0)PD0-Pad43)") (class "Default")
      (node (ref "IC3") (pin "43") (pinfunction "(SCL/INT0)PD0_43") (pintype "bidirectional"))
    )
    (net (code "93") (name "unconnected-(IC3-(SDA{slash}INT1)PD1-Pad44)") (class "Default")
      (node (ref "IC3") (pin "44") (pinfunction "(SDA/INT1)PD1_44") (pintype "bidirectional"))
    )
    (net (code "94") (name "unconnected-(IC3-(T1)PD6-Pad49)") (class "Default")
      (node (ref "IC3") (pin "49") (pinfunction "(T1)PD6_49") (pintype "bidirectional"))
    )
    (net (code "95") (name "unconnected-(IC3-(T3{slash}INT6)PE6-Pad8)") (class "Default")
      (node (ref "IC3") (pin "8") (pinfunction "(T3/INT6)PE6_8") (pintype "bidirectional"))
    )
    (net (code "96") (name "unconnected-(IC3-(TOSC1)PG4-Pad29)") (class "Default")
      (node (ref "IC3") (pin "29") (pinfunction "(TOSC1)PG4_29") (pintype "bidirectional"))
    )
    (net (code "97") (name "unconnected-(IC3-(TOSC2)PG3-Pad28)") (class "Default")
      (node (ref "IC3") (pin "28") (pinfunction "(TOSC2)PG3_28") (pintype "bidirectional"))
    )
    (net (code "98") (name "unconnected-(IC3-(XCK0{slash}AIN0)PE2-Pad4)") (class "Default")
      (node (ref "IC3") (pin "4") (pinfunction "(XCK0/AIN0)PE2_4") (pintype "bidirectional"))
    )
    (net (code "99") (name "unconnected-(IC3-(XCK1)PD5-Pad48)") (class "Default")
      (node (ref "IC3") (pin "48") (pinfunction "(XCK1)PD5_48") (pintype "bidirectional"))
    )
    (net (code "100") (name "unconnected-(IC3-PH2(XCK2)-Pad14)") (class "Default")
      (node (ref "IC3") (pin "14") (pinfunction "PH2(XCK2)_14") (pintype "bidirectional"))
    )
    (net (code "101") (name "unconnected-(IC3-PH7(T4)-Pad27)") (class "Default")
      (node (ref "IC3") (pin "27") (pinfunction "PH7(T4)_27") (pintype "bidirectional"))
    )
    (net (code "102") (name "unconnected-(IC3-PJ2(XCK3{slash}PCINT11)-Pad65)") (class "Default")
      (node (ref "IC3") (pin "65") (pinfunction "PJ2(XCK3/PCINT11)_65") (pintype "bidirectional"))
    )
    (net (code "103") (name "unconnected-(IC3-PJ3(PCINT12)-Pad66)") (class "Default")
      (node (ref "IC3") (pin "66") (pinfunction "PJ3(PCINT12)_66") (pintype "bidirectional"))
    )
    (net (code "104") (name "unconnected-(IC3-PJ4(PCINT13)-Pad67)") (class "Default")
      (node (ref "IC3") (pin "67") (pinfunction "PJ4(PCINT13)_67") (pintype "bidirectional"))
    )
    (net (code "105") (name "unconnected-(IC3-PJ5(PCINT14)-Pad68)") (class "Default")
      (node (ref "IC3") (pin "68") (pinfunction "PJ5(PCINT14)_68") (pintype "bidirectional"))
    )
    (net (code "106") (name "unconnected-(IC3-PJ6(PCINT15)-Pad69)") (class "Default")
      (node (ref "IC3") (pin "69") (pinfunction "PJ6(PCINT15)_69") (pintype "bidirectional"))
    )
    (net (code "107") (name "unconnected-(IC3-PJ7-Pad79)") (class "Default")
      (node (ref "IC3") (pin "79") (pinfunction "PJ7_79") (pintype "bidirectional"))
    )
  )
)
